# sensor_distancia.net
KiCad netlist of a schematic drawn in EAGLE
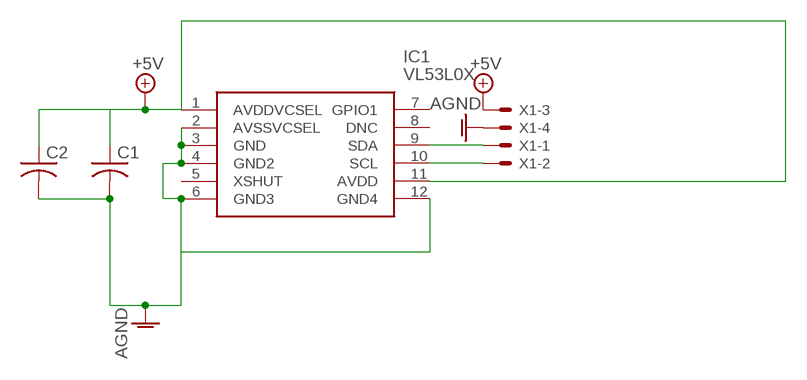
[diagram p0: schematic, sheet 1]

(export (version "E")
  (design (tool "Eeschema 10.0.6"))
  (components
    (comp (ref "C1")
      (value "C-US025-025X050")
      (footprint "eagle-import:C025-025X050")
      (libsource (lib "eagle-import") (part "C-US025-025X050"))
    )
    (comp (ref "C2")
      (value "C-US025-025X050")
      (footprint "eagle-import:C025-025X050")
      (libsource (lib "eagle-import") (part "C-US025-025X050"))
    )
    (comp (ref "IC1")
      (value "VL53L0X")
      (footprint "eagle-import:VL53L0X")
      (libsource (lib "eagle-import") (part "VL53L0X"))
    )
    (comp (ref "X1")
      (value "KK-156-4")
      (footprint "eagle-import:KK-156-4")
      (fields (field (name "MF") "MOLEX"))
      (libsource (lib "eagle-import") (part "KK-156-4"))
    )
  )
  (nets
    (net (code "1") (name "+5V") (class "Default")
      (node (ref "C1") (pin "1") (pinfunction "1_1") (pintype "passive"))
      (node (ref "C2") (pin "1") (pinfunction "1_1") (pintype "passive"))
      (node (ref "IC1") (pin "1") (pinfunction "AVDDVCSEL_1") (pintype "bidirectional"))
      (node (ref "IC1") (pin "11") (pinfunction "AVDD_11") (pintype "bidirectional"))
      (node (ref "X1") (pin "3") (pinfunction "S_3") (pintype "passive"))
    )
    (net (code "2") (name "AGND") (class "Default")
      (node (ref "C1") (pin "2") (pinfunction "2_2") (pintype "passive"))
      (node (ref "C2") (pin "2") (pinfunction "2_2") (pintype "passive"))
      (node (ref "IC1") (pin "12") (pinfunction "GND4_12") (pintype "bidirectional"))
      (node (ref "IC1") (pin "2") (pinfunction "AVSSVCSEL_2") (pintype "bidirectional"))
      (node (ref "IC1") (pin "3") (pinfunction "GND_3") (pintype "bidirectional"))
      (node (ref "IC1") (pin "4") (pinfunction "GND2_4") (pintype "bidirectional"))
      (node (ref "IC1") (pin "6") (pinfunction "GND3_6") (pintype "bidirectional"))
      (node (ref "X1") (pin "4") (pinfunction "S_4") (pintype "passive"))
    )
    (net (code "3") (name "Net-(IC1-SCL)") (class "Default")
      (node (ref "IC1") (pin "10") (pinfunction "SCL_10") (pintype "bidirectional"))
      (node (ref "X1") (pin "2") (pinfunction "S_2") (pintype "passive"))
    )
    (net (code "4") (name "Net-(IC1-SDA)") (class "Default")
      (node (ref "IC1") (pin "9") (pinfunction "SDA_9") (pintype "bidirectional"))
      (node (ref "X1") (pin "1") (pinfunction "S_1") (pintype "passive"))
    )
    (net (code "5") (name "unconnected-(IC1-DNC-Pad8)") (class "Default")
      (node (ref "IC1") (pin "8") (pinfunction "DNC_8") (pintype "bidirectional"))
    )
    (net (code "6") (name "unconnected-(IC1-GPIO1-Pad7)") (class "Default")
      (node (ref "IC1") (pin "7") (pinfunction "GPIO1_7") (pintype "bidirectional"))
    )
    (net (code "7") (name "unconnected-(IC1-XSHUT-Pad5)") (class "Default")
      (node (ref "IC1") (pin "5") (pinfunction "XSHUT_5") (pintype "bidirectional"))
    )
  )
)
